# RCMx1_Rev_05.net
KiCad netlist of a schematic drawn in EAGLE
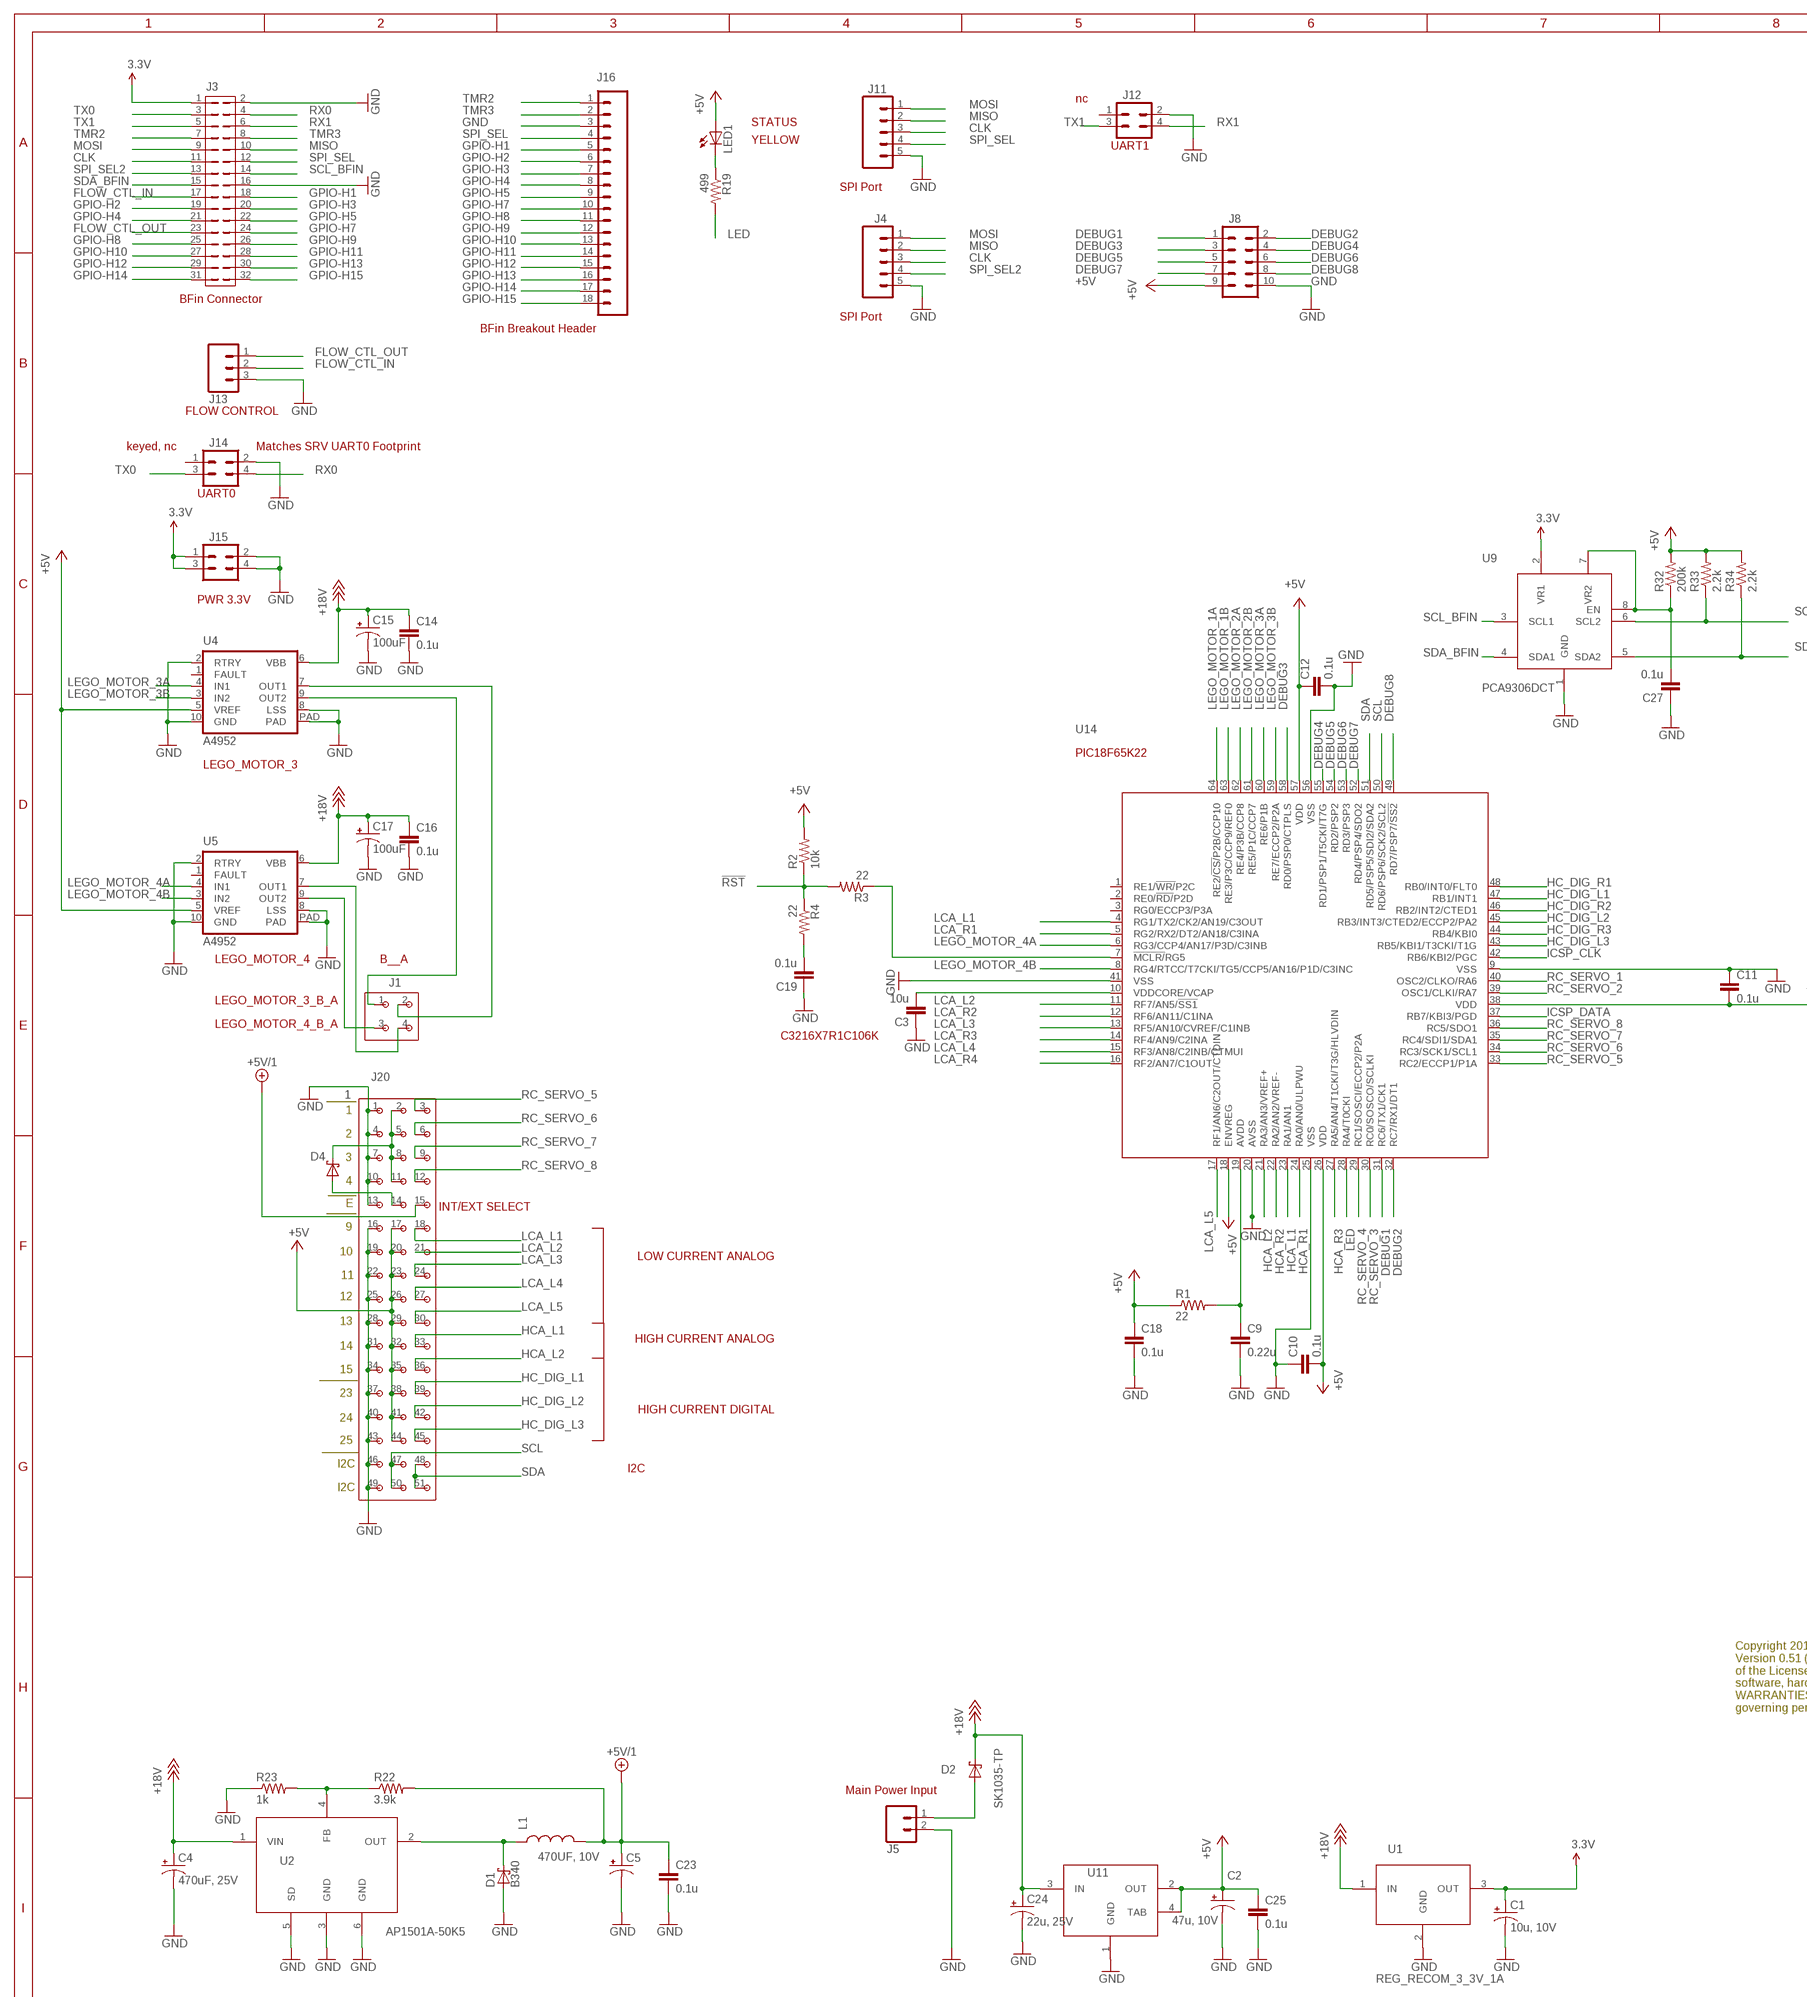
[diagram p0: schematic, sheet 1, part 1 of 2]
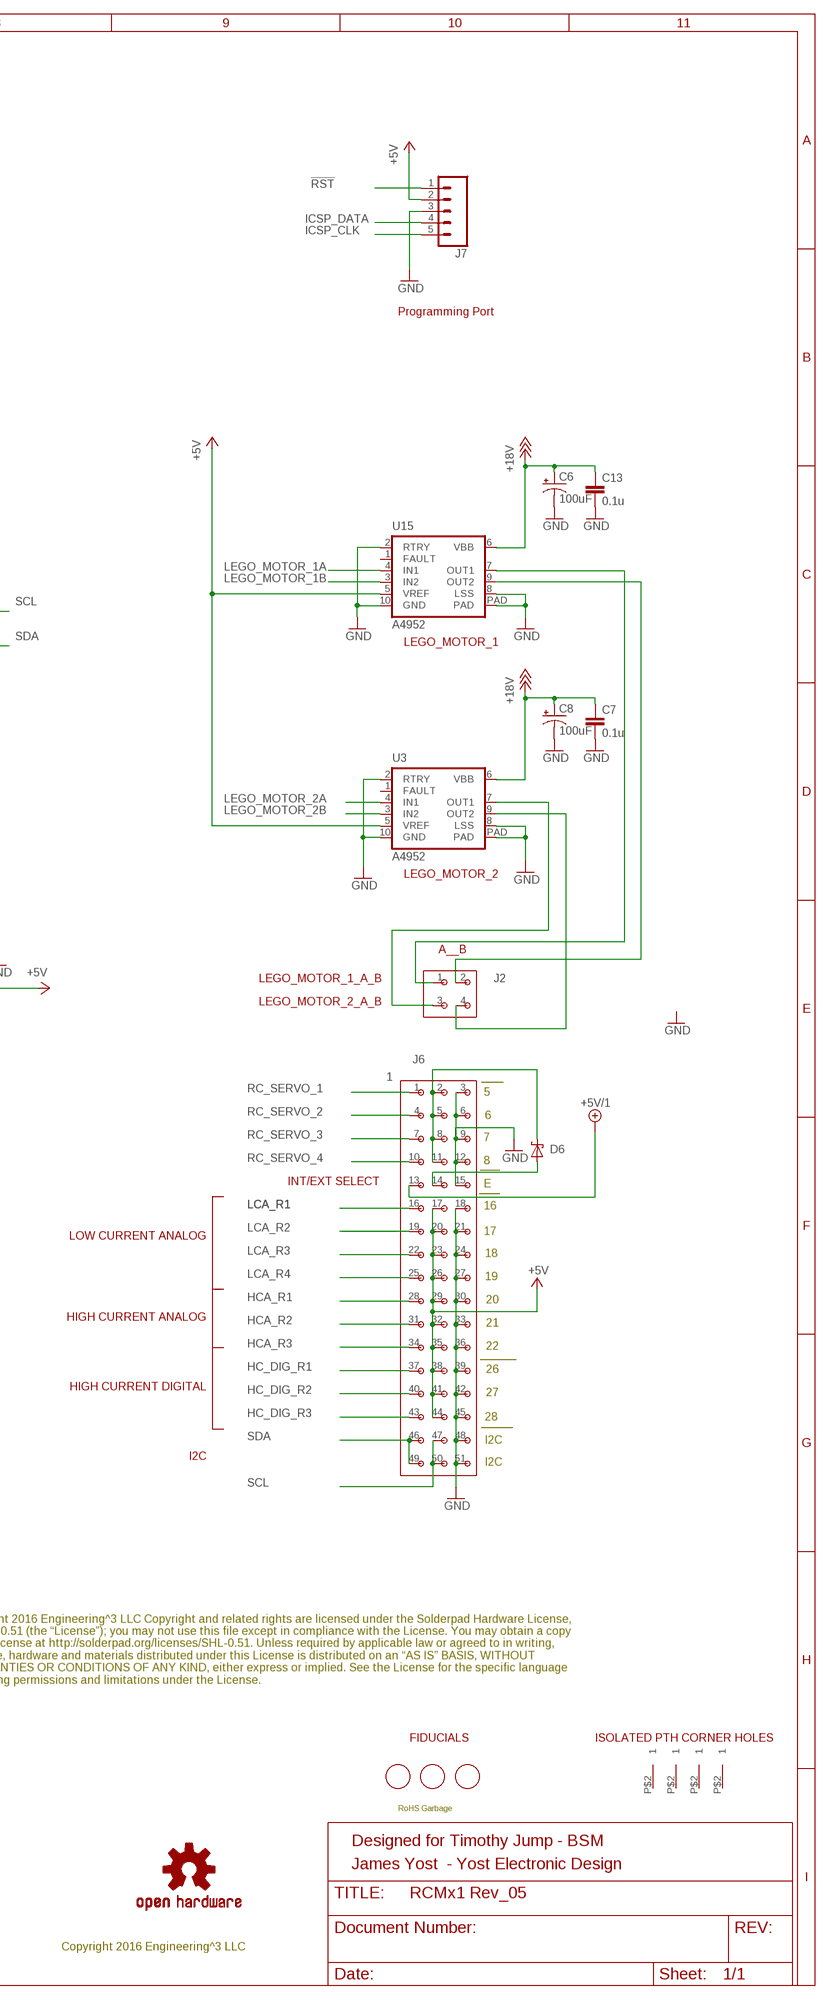
[diagram p1: schematic, sheet 1, part 2 of 2]

(export (version "E")
  (design (tool "Eeschema 10.0.6"))
  (components
    (comp (ref "C1")
      (value "10u, 10V")
      (footprint "eagle-import:EIA3216")
      (libsource (lib "eagle-import") (part "CAP_POL1206"))
    )
    (comp (ref "C2")
      (value "47u, 10V")
      (footprint "eagle-import:CAP1210_POL")
      (libsource (lib "eagle-import") (part "CAP_1210_POL"))
    )
    (comp (ref "C3")
      (value "10u")
      (footprint "eagle-import:1206")
      (libsource (lib "eagle-import") (part "CAP1206"))
    )
    (comp (ref "C4")
      (value "470uF, 25V")
      (footprint "eagle-import:PANASONIC_G")
      (libsource (lib "eagle-import") (part "CAP_POLG"))
    )
    (comp (ref "C5")
      (value "470UF, 10V")
      (footprint "eagle-import:PANASONIC_F")
      (libsource (lib "eagle-import") (part "CAP_ELT_PANASONIC_470UF"))
    )
    (comp (ref "C6")
      (value "100uF")
      (footprint "eagle-import:PANASONIC_D")
      (libsource (lib "eagle-import") (part "CAP_POLD"))
    )
    (comp (ref "C7")
      (value "0.1u")
      (footprint "eagle-import:0805")
      (libsource (lib "eagle-import") (part "CAP0805"))
    )
    (comp (ref "C8")
      (value "100uF")
      (footprint "eagle-import:PANASONIC_D")
      (libsource (lib "eagle-import") (part "CAP_POLD"))
    )
    (comp (ref "C9")
      (value "0.22u")
      (footprint "eagle-import:0805")
      (libsource (lib "eagle-import") (part "CAP0805"))
    )
    (comp (ref "C10")
      (value "0.1u")
      (footprint "eagle-import:0805")
      (libsource (lib "eagle-import") (part "CAP0805"))
    )
    (comp (ref "C11")
      (value "0.1u")
      (footprint "eagle-import:0805")
      (libsource (lib "eagle-import") (part "CAP0805"))
    )
    (comp (ref "C12")
      (value "0.1u")
      (footprint "eagle-import:0805")
      (libsource (lib "eagle-import") (part "CAP0805"))
    )
    (comp (ref "C13")
      (value "0.1u")
      (footprint "eagle-import:0805")
      (libsource (lib "eagle-import") (part "CAP0805"))
    )
    (comp (ref "C14")
      (value "0.1u")
      (footprint "eagle-import:0805")
      (libsource (lib "eagle-import") (part "CAP0805"))
    )
    (comp (ref "C15")
      (value "100uF")
      (footprint "eagle-import:PANASONIC_D")
      (libsource (lib "eagle-import") (part "CAP_POLD"))
    )
    (comp (ref "C16")
      (value "0.1u")
      (footprint "eagle-import:0805")
      (libsource (lib "eagle-import") (part "CAP0805"))
    )
    (comp (ref "C17")
      (value "100uF")
      (footprint "eagle-import:PANASONIC_D")
      (libsource (lib "eagle-import") (part "CAP_POLD"))
    )
    (comp (ref "C18")
      (value "0.1u")
      (footprint "eagle-import:0805")
      (libsource (lib "eagle-import") (part "CAP0805"))
    )
    (comp (ref "C19")
      (value "0.1u")
      (footprint "eagle-import:0805")
      (libsource (lib "eagle-import") (part "CAP0805"))
    )
    (comp (ref "C23")
      (value "0.1u")
      (footprint "eagle-import:0805")
      (libsource (lib "eagle-import") (part "CAP0805"))
    )
    (comp (ref "C24")
      (value "22u, 25V")
      (footprint "eagle-import:CAP1210_POL")
      (libsource (lib "eagle-import") (part "CAP_1210_POL"))
    )
    (comp (ref "C25")
      (value "0.1u")
      (footprint "eagle-import:0805")
      (libsource (lib "eagle-import") (part "CAP0805"))
    )
    (comp (ref "C27")
      (value "0.1u")
      (footprint "eagle-import:0805")
      (libsource (lib "eagle-import") (part "CAP0805"))
    )
    (comp (ref "D1")
      (value "B340")
      (footprint "eagle-import:SMA_DO214AC")
      (libsource (lib "eagle-import") (part "B340"))
    )
    (comp (ref "D2")
      (value "SK1035-TP")
      (footprint "eagle-import:DO214AB")
      (libsource (lib "eagle-import") (part "SK1035-TP"))
    )
    (comp (ref "D4")
      (value "SK1035-TP")
      (footprint "eagle-import:DO214AB")
      (libsource (lib "eagle-import") (part "SK1035-TP"))
    )
    (comp (ref "D6")
      (value "SK1035-TP")
      (footprint "eagle-import:DO214AB")
      (libsource (lib "eagle-import") (part "SK1035-TP"))
    )
    (comp (ref "FID1")
      (value "FIDUCIAL")
      (footprint "eagle-import:FIDUCIAL_1MM")
      (libsource (lib "eagle-import") (part "FIDUCIAL"))
    )
    (comp (ref "FID2")
      (value "FIDUCIAL")
      (footprint "eagle-import:FIDUCIAL_1MM")
      (libsource (lib "eagle-import") (part "FIDUCIAL"))
    )
    (comp (ref "FID3")
      (value "FIDUCIAL")
      (footprint "eagle-import:FIDUCIAL_1MM")
      (libsource (lib "eagle-import") (part "FIDUCIAL"))
    )
    (comp (ref "J1")
      (value "CON_2X2_0_100")
      (footprint "eagle-import:CON_2X2_0_100")
      (libsource (lib "eagle-import") (part "CON_2X2_0_100"))
    )
    (comp (ref "J2")
      (value "CON_2X2_0_100")
      (footprint "eagle-import:CON_2X2_0_100")
      (libsource (lib "eagle-import") (part "CON_2X2_0_100"))
    )
    (comp (ref "J3")
      (value "CON_2X16_0_100")
      (footprint "eagle-import:CON_2X16_0_100")
      (libsource (lib "eagle-import") (part "CON_2X16_0_100"))
    )
    (comp (ref "J4")
      (value "M05PTH")
      (footprint "eagle-import:1X05")
      (libsource (lib "eagle-import") (part "M05PTH"))
    )
    (comp (ref "J5")
      (value "M02NG")
      (footprint "eagle-import:1X02")
      (libsource (lib "eagle-import") (part "M02NG"))
    )
    (comp (ref "J6")
      (value "CON_3X17_0_100")
      (footprint "eagle-import:CON_3X17_0_100")
      (libsource (lib "eagle-import") (part "CON_3X17_0_100"))
    )
    (comp (ref "J7")
      (value "M05PTH")
      (footprint "eagle-import:1X05")
      (libsource (lib "eagle-import") (part "SparkFun-Connectors_M05PTH"))
    )
    (comp (ref "J8")
      (value "M05X2PTH")
      (footprint "eagle-import:AVR_ICSP")
      (libsource (lib "eagle-import") (part "M05X2PTH"))
    )
    (comp (ref "J11")
      (value "M05PTH")
      (footprint "eagle-import:1X05")
      (libsource (lib "eagle-import") (part "M05PTH"))
    )
    (comp (ref "J12")
      (value "CON2X2")
      (footprint "eagle-import:CON2X2")
      (libsource (lib "eagle-import") (part "CON2X2"))
    )
    (comp (ref "J13")
      (value "M03PTH")
      (footprint "eagle-import:1X03")
      (libsource (lib "eagle-import") (part "M03PTH"))
    )
    (comp (ref "J14")
      (value "CON2X2")
      (footprint "eagle-import:CON2X2")
      (libsource (lib "eagle-import") (part "CON2X2"))
    )
    (comp (ref "J15")
      (value "CON2X2")
      (footprint "eagle-import:CON2X2")
      (libsource (lib "eagle-import") (part "CON2X2"))
    )
    (comp (ref "J16")
      (value "CON1X18")
      (footprint "eagle-import:CON1X18")
      (libsource (lib "eagle-import") (part "CON1X18"))
    )
    (comp (ref "J20")
      (value "CON_3X17_0_100")
      (footprint "eagle-import:CON_3X17_0_100")
      (libsource (lib "eagle-import") (part "CON_3X17_0_100"))
    )
    (comp (ref "L1")
      (value "IND_47UH_COILTRONICS_2_95A")
      (footprint "eagle-import:IND_PADS_SMT")
      (libsource (lib "eagle-import") (part "IND_47UH_COILTRONICS_2_95A"))
    )
    (comp (ref "LED1")
      (value "LEDCHIP-LED0805")
      (footprint "eagle-import:CHIP-LED0805")
      (libsource (lib "eagle-import") (part "LEDCHIP-LED0805"))
    )
    (comp (ref "LOGO3")
      (value "OSHW-LOGOM")
      (footprint "eagle-import:OSHW-LOGO-M")
      (libsource (lib "eagle-import") (part "OSHW-LOGOM"))
    )
    (comp (ref "R1")
      (value "22")
      (footprint "eagle-import:0805")
      (libsource (lib "eagle-import") (part "RESISTOR"))
    )
    (comp (ref "R2")
      (value "10k")
      (footprint "eagle-import:0805")
      (libsource (lib "eagle-import") (part "RESISTOR"))
    )
    (comp (ref "R3")
      (value "22")
      (footprint "eagle-import:0805")
      (libsource (lib "eagle-import") (part "RESISTOR"))
    )
    (comp (ref "R4")
      (value "22")
      (footprint "eagle-import:0805")
      (libsource (lib "eagle-import") (part "RESISTOR"))
    )
    (comp (ref "R19")
      (value "499")
      (footprint "eagle-import:0805")
      (libsource (lib "eagle-import") (part "RESISTOR"))
    )
    (comp (ref "R22")
      (value "3.9k")
      (footprint "eagle-import:0805")
      (libsource (lib "eagle-import") (part "RESISTOR"))
    )
    (comp (ref "R23")
      (value "1k")
      (footprint "eagle-import:0805")
      (libsource (lib "eagle-import") (part "RESISTOR"))
    )
    (comp (ref "R32")
      (value "200k")
      (footprint "eagle-import:0805")
      (libsource (lib "eagle-import") (part "RESISTOR"))
    )
    (comp (ref "R33")
      (value "2.2k")
      (footprint "eagle-import:0805")
      (libsource (lib "eagle-import") (part "RESISTOR"))
    )
    (comp (ref "R34")
      (value "2.2k")
      (footprint "eagle-import:0805")
      (libsource (lib "eagle-import") (part "RESISTOR"))
    )
    (comp (ref "U$1")
      (value "GNDPAD")
      (footprint "eagle-import:GNDPAD")
      (libsource (lib "eagle-import") (part "GNDPAD"))
    )
    (comp (ref "U$2")
      (value "GNDPAD")
      (footprint "eagle-import:GNDPAD")
      (libsource (lib "eagle-import") (part "GNDPAD"))
    )
    (comp (ref "U$3")
      (value "ROHS_GARBAGE")
      (footprint "eagle-import:ROHS_GARBAGE_5MM")
      (libsource (lib "eagle-import") (part "ROHS_GARBAGE"))
    )
    (comp (ref "U$7")
      (value "GNDPAD")
      (footprint "eagle-import:GNDPAD")
      (libsource (lib "eagle-import") (part "GNDPAD"))
    )
    (comp (ref "U$8")
      (value "GNDPAD")
      (footprint "eagle-import:GNDPAD")
      (libsource (lib "eagle-import") (part "GNDPAD"))
    )
    (comp (ref "U1")
      (value "REG_RECOM_3_3V_1A")
      (footprint "eagle-import:REG_RECOM_3_3V_1A")
      (libsource (lib "eagle-import") (part "REG_RECOM_3_3V_1A"))
    )
    (comp (ref "U2")
      (value "AP1501A-50K5")
      (footprint "eagle-import:TO263-5")
      (libsource (lib "eagle-import") (part "AP1501A-50K5"))
    )
    (comp (ref "U3")
      (value "A4952")
      (footprint "eagle-import:MSOP10_W_THERMAL_PAD")
      (libsource (lib "eagle-import") (part "A4952"))
    )
    (comp (ref "U4")
      (value "A4952")
      (footprint "eagle-import:MSOP10_W_THERMAL_PAD")
      (libsource (lib "eagle-import") (part "A4952"))
    )
    (comp (ref "U5")
      (value "A4952")
      (footprint "eagle-import:MSOP10_W_THERMAL_PAD")
      (libsource (lib "eagle-import") (part "A4952"))
    )
    (comp (ref "U9")
      (value "PCA9306DCT")
      (footprint "eagle-import:TEST08")
      (libsource (lib "eagle-import") (part "PCA9306DCT"))
    )
    (comp (ref "U11")
      (value "TLV1117-5")
      (footprint "eagle-import:SOT223")
      (libsource (lib "eagle-import") (part "TLV1117-5"))
    )
    (comp (ref "U14")
      (value "MICRO_C_PIC18F65K22")
      (footprint "eagle-import:64PIN_TQFP_10X10X1MM")
      (libsource (lib "eagle-import") (part "MICRO_C_PIC18F65K22"))
    )
    (comp (ref "U15")
      (value "A4952")
      (footprint "eagle-import:MSOP10_W_THERMAL_PAD")
      (libsource (lib "eagle-import") (part "A4952"))
    )
  )
  (nets
    (net (code "1") (name "+5V") (class "Default")
      (node (ref "C10") (pin "2") (pinfunction "2_2") (pintype "passive"))
      (node (ref "C11") (pin "2") (pinfunction "2_2") (pintype "passive"))
      (node (ref "C12") (pin "1") (pinfunction "1_1") (pintype "passive"))
      (node (ref "C18") (pin "1") (pinfunction "1_1") (pintype "passive"))
      (node (ref "C2") (pin "1") (pinfunction "+_1") (pintype "passive"))
      (node (ref "C25") (pin "1") (pinfunction "1_1") (pintype "passive"))
      (node (ref "J20") (pin "17") (pinfunction "17_17") (pintype "passive"))
      (node (ref "J20") (pin "20") (pinfunction "20_20") (pintype "passive"))
      (node (ref "J20") (pin "23") (pinfunction "23_23") (pintype "passive"))
      (node (ref "J20") (pin "26") (pinfunction "26_26") (pintype "passive"))
      (node (ref "J20") (pin "29") (pinfunction "29_29") (pintype "passive"))
      (node (ref "J20") (pin "32") (pinfunction "32_32") (pintype "passive"))
      (node (ref "J20") (pin "35") (pinfunction "35_35") (pintype "passive"))
      (node (ref "J20") (pin "38") (pinfunction "38_38") (pintype "passive"))
      (node (ref "J20") (pin "41") (pinfunction "41_41") (pintype "passive"))
      (node (ref "J20") (pin "44") (pinfunction "44_44") (pintype "passive"))
      (node (ref "J6") (pin "17") (pinfunction "17_17") (pintype "passive"))
      (node (ref "J6") (pin "20") (pinfunction "20_20") (pintype "passive"))
      (node (ref "J6") (pin "23") (pinfunction "23_23") (pintype "passive"))
      (node (ref "J6") (pin "26") (pinfunction "26_26") (pintype "passive"))
      (node (ref "J6") (pin "29") (pinfunction "29_29") (pintype "passive"))
      (node (ref "J6") (pin "32") (pinfunction "32_32") (pintype "passive"))
      (node (ref "J6") (pin "35") (pinfunction "35_35") (pintype "passive"))
      (node (ref "J6") (pin "38") (pinfunction "38_38") (pintype "passive"))
      (node (ref "J6") (pin "41") (pinfunction "41_41") (pintype "passive"))
      (node (ref "J6") (pin "44") (pinfunction "44_44") (pintype "passive"))
      (node (ref "J7") (pin "2") (pinfunction "2_2") (pintype "passive"))
      (node (ref "J8") (pin "9") (pinfunction "9_9") (pintype "passive"))
      (node (ref "LED1") (pin "A") (pinfunction "A_A") (pintype "passive"))
      (node (ref "R1") (pin "1") (pinfunction "1_1") (pintype "passive"))
      (node (ref "R2") (pin "2") (pinfunction "2_2") (pintype "passive"))
      (node (ref "R32") (pin "2") (pinfunction "2_2") (pintype "passive"))
      (node (ref "R33") (pin "2") (pinfunction "2_2") (pintype "passive"))
      (node (ref "R34") (pin "2") (pinfunction "2_2") (pintype "passive"))
      (node (ref "U11") (pin "2") (pinfunction "OUT_2") (pintype "bidirectional"))
      (node (ref "U11") (pin "4") (pinfunction "TAB_4") (pintype "bidirectional"))
      (node (ref "U14") (pin "18") (pinfunction "ENVREG_18") (pintype "input"))
      (node (ref "U14") (pin "26") (pinfunction "VDD_26") (pintype "power_in"))
      (node (ref "U14") (pin "38") (pinfunction "VDD_38") (pintype "power_in"))
      (node (ref "U14") (pin "57") (pinfunction "VDD_57") (pintype "power_in"))
      (node (ref "U15") (pin "5") (pinfunction "VREF_5") (pintype "passive"))
      (node (ref "U3") (pin "5") (pinfunction "VREF_5") (pintype "passive"))
      (node (ref "U4") (pin "5") (pinfunction "VREF_5") (pintype "passive"))
      (node (ref "U5") (pin "5") (pinfunction "VREF_5") (pintype "passive"))
    )
    (net (code "2") (name "+5V{slash}1") (class "Default")
      (node (ref "C23") (pin "1") (pinfunction "1_1") (pintype "passive"))
      (node (ref "C5") (pin "+") (pinfunction "+_+") (pintype "passive"))
      (node (ref "J20") (pin "15") (pinfunction "15_15") (pintype "passive"))
      (node (ref "J6") (pin "13") (pinfunction "13_13") (pintype "passive"))
      (node (ref "L1") (pin "2") (pinfunction "2_2") (pintype "passive"))
      (node (ref "R22") (pin "2") (pinfunction "2_2") (pintype "passive"))
    )
    (net (code "3") (name "+18V") (class "Default")
      (node (ref "C13") (pin "1") (pinfunction "1_1") (pintype "passive"))
      (node (ref "C14") (pin "1") (pinfunction "1_1") (pintype "passive"))
      (node (ref "C15") (pin "+") (pinfunction "+_+") (pintype "passive"))
      (node (ref "C16") (pin "1") (pinfunction "1_1") (pintype "passive"))
      (node (ref "C17") (pin "+") (pinfunction "+_+") (pintype "passive"))
      (node (ref "C24") (pin "1") (pinfunction "+_1") (pintype "passive"))
      (node (ref "C4") (pin "+") (pinfunction "+_+") (pintype "passive"))
      (node (ref "C6") (pin "+") (pinfunction "+_+") (pintype "passive"))
      (node (ref "C7") (pin "1") (pinfunction "1_1") (pintype "passive"))
      (node (ref "C8") (pin "+") (pinfunction "+_+") (pintype "passive"))
      (node (ref "D2") (pin "1") (pinfunction "C_1") (pintype "passive"))
      (node (ref "U1") (pin "1") (pinfunction "IN_1") (pintype "bidirectional"))
      (node (ref "U11") (pin "3") (pinfunction "IN_3") (pintype "bidirectional"))
      (node (ref "U15") (pin "6") (pinfunction "VBB_6") (pintype "input"))
      (node (ref "U2") (pin "1") (pinfunction "VIN_1") (pintype "bidirectional"))
      (node (ref "U3") (pin "6") (pinfunction "VBB_6") (pintype "input"))
      (node (ref "U4") (pin "6") (pinfunction "VBB_6") (pintype "input"))
      (node (ref "U5") (pin "6") (pinfunction "VBB_6") (pintype "input"))
    )
    (net (code "4") (name "/CLK") (class "Default")
      (node (ref "J11") (pin "3") (pinfunction "3_3") (pintype "passive"))
      (node (ref "J3") (pin "11") (pinfunction "11_11") (pintype "passive"))
      (node (ref "J4") (pin "3") (pinfunction "3_3") (pintype "passive"))
    )
    (net (code "5") (name "/DEBUG1") (class "Default")
      (node (ref "J8") (pin "1") (pinfunction "1_1") (pintype "passive"))
      (node (ref "U14") (pin "31") (pinfunction "RC6/TX1/CK1_31") (pintype "bidirectional"))
    )
    (net (code "6") (name "/DEBUG2") (class "Default")
      (node (ref "J8") (pin "2") (pinfunction "2_2") (pintype "passive"))
      (node (ref "U14") (pin "32") (pinfunction "RC7/RX1/DT1_32") (pintype "bidirectional"))
    )
    (net (code "7") (name "/DEBUG3") (class "Default")
      (node (ref "J8") (pin "3") (pinfunction "3_3") (pintype "passive"))
      (node (ref "U14") (pin "58") (pinfunction "RD0/PSP0/CTPLS_58") (pintype "bidirectional"))
    )
    (net (code "8") (name "/DEBUG4") (class "Default")
      (node (ref "J8") (pin "4") (pinfunction "4_4") (pintype "passive"))
      (node (ref "U14") (pin "55") (pinfunction "RD1/PSP1/T5CKI/T7G_55") (pintype "bidirectional"))
    )
    (net (code "9") (name "/DEBUG5") (class "Default")
      (node (ref "J8") (pin "5") (pinfunction "5_5") (pintype "passive"))
      (node (ref "U14") (pin "54") (pinfunction "RD2/PSP2_54") (pintype "bidirectional"))
    )
    (net (code "10") (name "/DEBUG6") (class "Default")
      (node (ref "J8") (pin "6") (pinfunction "6_6") (pintype "passive"))
      (node (ref "U14") (pin "53") (pinfunction "RD3/PSP3_53") (pintype "bidirectional"))
    )
    (net (code "11") (name "/DEBUG7") (class "Default")
      (node (ref "J8") (pin "7") (pinfunction "7_7") (pintype "passive"))
      (node (ref "U14") (pin "52") (pinfunction "RD4/PSP4/SDO2_52") (pintype "bidirectional"))
    )
    (net (code "12") (name "/DEBUG8") (class "Default")
      (node (ref "J8") (pin "8") (pinfunction "8_8") (pintype "passive"))
      (node (ref "U14") (pin "49") (pinfunction "RD7/PSP7/~{SS2}_49") (pintype "bidirectional"))
    )
    (net (code "13") (name "/FLOW_CTL_IN") (class "Default")
      (node (ref "J13") (pin "2") (pinfunction "2_2") (pintype "passive"))
      (node (ref "J3") (pin "17") (pinfunction "17_17") (pintype "passive"))
    )
    (net (code "14") (name "/FLOW_CTL_OUT") (class "Default")
      (node (ref "J13") (pin "1") (pinfunction "1_1") (pintype "passive"))
      (node (ref "J3") (pin "23") (pinfunction "23_23") (pintype "passive"))
    )
    (net (code "15") (name "/GPIO-H1") (class "Default")
      (node (ref "J16") (pin "5") (pinfunction "5_5") (pintype "passive"))
      (node (ref "J3") (pin "18") (pinfunction "18_18") (pintype "passive"))
    )
    (net (code "16") (name "/GPIO-H2") (class "Default")
      (node (ref "J16") (pin "6") (pinfunction "6_6") (pintype "passive"))
      (node (ref "J3") (pin "19") (pinfunction "19_19") (pintype "passive"))
    )
    (net (code "17") (name "/GPIO-H3") (class "Default")
      (node (ref "J16") (pin "7") (pinfunction "7_7") (pintype "passive"))
      (node (ref "J3") (pin "20") (pinfunction "20_20") (pintype "passive"))
    )
    (net (code "18") (name "/GPIO-H4") (class "Default")
      (node (ref "J16") (pin "8") (pinfunction "8_8") (pintype "passive"))
      (node (ref "J3") (pin "21") (pinfunction "21_21") (pintype "passive"))
    )
    (net (code "19") (name "/GPIO-H5") (class "Default")
      (node (ref "J16") (pin "9") (pinfunction "9_9") (pintype "passive"))
      (node (ref "J3") (pin "22") (pinfunction "22_22") (pintype "passive"))
    )
    (net (code "20") (name "/GPIO-H7") (class "Default")
      (node (ref "J16") (pin "10") (pinfunction "10_10") (pintype "passive"))
      (node (ref "J3") (pin "24") (pinfunction "24_24") (pintype "passive"))
    )
    (net (code "21") (name "/GPIO-H8") (class "Default")
      (node (ref "J16") (pin "11") (pinfunction "11_11") (pintype "passive"))
      (node (ref "J3") (pin "25") (pinfunction "25_25") (pintype "passive"))
    )
    (net (code "22") (name "/GPIO-H9") (class "Default")
      (node (ref "J16") (pin "12") (pinfunction "12_12") (pintype "passive"))
      (node (ref "J3") (pin "26") (pinfunction "26_26") (pintype "passive"))
    )
    (net (code "23") (name "/GPIO-H10") (class "Default")
      (node (ref "J16") (pin "13") (pinfunction "13_13") (pintype "passive"))
      (node (ref "J3") (pin "27") (pinfunction "27_27") (pintype "passive"))
    )
    (net (code "24") (name "/GPIO-H11") (class "Default")
      (node (ref "J16") (pin "14") (pinfunction "14_14") (pintype "passive"))
      (node (ref "J3") (pin "28") (pinfunction "28_28") (pintype "passive"))
    )
    (net (code "25") (name "/GPIO-H12") (class "Default")
      (node (ref "J16") (pin "15") (pinfunction "15_15") (pintype "passive"))
      (node (ref "J3") (pin "29") (pinfunction "29_29") (pintype "passive"))
    )
    (net (code "26") (name "/GPIO-H13") (class "Default")
      (node (ref "J16") (pin "16") (pinfunction "16_16") (pintype "passive"))
      (node (ref "J3") (pin "30") (pinfunction "30_30") (pintype "passive"))
    )
    (net (code "27") (name "/GPIO-H14") (class "Default")
      (node (ref "J16") (pin "17") (pinfunction "17_17") (pintype "passive"))
      (node (ref "J3") (pin "31") (pinfunction "31_31") (pintype "passive"))
    )
    (net (code "28") (name "/GPIO-H15") (class "Default")
      (node (ref "J16") (pin "18") (pinfunction "18_18") (pintype "passive"))
      (node (ref "J3") (pin "32") (pinfunction "32_32") (pintype "passive"))
    )
    (net (code "29") (name "/HCA_L1") (class "Default")
      (node (ref "J20") (pin "33") (pinfunction "33_33") (pintype "passive"))
      (node (ref "U14") (pin "23") (pinfunction "RA1/AN1_23") (pintype "bidirectional"))
    )
    (net (code "30") (name "/HCA_L2") (class "Default")
      (node (ref "J20") (pin "36") (pinfunction "36_36") (pintype "passive"))
      (node (ref "U14") (pin "21") (pinfunction "RA3/AN3/VREF+_21") (pintype "bidirectional"))
    )
    (net (code "31") (name "/HCA_R1") (class "Default")
      (node (ref "J6") (pin "28") (pinfunction "28_28") (pintype "passive"))
      (node (ref "U14") (pin "24") (pinfunction "RA0/AN0/ULPWU_24") (pintype "bidirectional"))
    )
    (net (code "32") (name "/HCA_R2") (class "Default")
      (node (ref "J6") (pin "31") (pinfunction "31_31") (pintype "passive"))
      (node (ref "U14") (pin "22") (pinfunction "RA2/AN2/VREF-_22") (pintype "bidirectional"))
    )
    (net (code "33") (name "/HCA_R3") (class "Default")
      (node (ref "J6") (pin "34") (pinfunction "34_34") (pintype "passive"))
      (node (ref "U14") (pin "27") (pinfunction "RA5/AN4/T1CKI/T3G/HLVDIN_27") (pintype "bidirectional"))
    )
    (net (code "34") (name "/HC_DIG_L1") (class "Default")
      (node (ref "J20") (pin "39") (pinfunction "39_39") (pintype "passive"))
      (node (ref "U14") (pin "47") (pinfunction "RB1/INT1_47") (pintype "bidirectional"))
    )
    (net (code "35") (name "/HC_DIG_L2") (class "Default")
      (node (ref "J20") (pin "42") (pinfunction "42_42") (pintype "passive"))
      (node (ref "U14") (pin "45") (pinfunction "RB3/INT3/CTED2/ECCP2/PA2_45") (pintype "bidirectional"))
    )
    (net (code "36") (name "/HC_DIG_L3") (class "Default")
      (node (ref "J20") (pin "45") (pinfunction "45_45") (pintype "passive"))
      (node (ref "U14") (pin "43") (pinfunction "RB5/KBI1/T3CKI/T1G_43") (pintype "bidirectional"))
    )
    (net (code "37") (name "/HC_DIG_R1") (class "Default")
      (node (ref "J6") (pin "37") (pinfunction "37_37") (pintype "passive"))
      (node (ref "U14") (pin "48") (pinfunction "RB0/INT0/FLT0_48") (pintype "bidirectional"))
    )
    (net (code "38") (name "/HC_DIG_R2") (class "Default")
      (node (ref "J6") (pin "40") (pinfunction "40_40") (pintype "passive"))
      (node (ref "U14") (pin "46") (pinfunction "RB2/INT2/CTED1_46") (pintype "bidirectional"))
    )
    (net (code "39") (name "/HC_DIG_R3") (class "Default")
      (node (ref "J6") (pin "43") (pinfunction "43_43") (pintype "passive"))
      (node (ref "U14") (pin "44") (pinfunction "RB4/KBI0_44") (pintype "bidirectional"))
    )
    (net (code "40") (name "/ICSP_CLK") (class "Default")
      (node (ref "J7") (pin "5") (pinfunction "5_5") (pintype "passive"))
      (node (ref "U14") (pin "42") (pinfunction "RB6/KBI2/PGC_42") (pintype "bidirectional"))
    )
    (net (code "41") (name "/ICSP_DATA") (class "Default")
      (node (ref "J7") (pin "4") (pinfunction "4_4") (pintype "passive"))
      (node (ref "U14") (pin "37") (pinfunction "RB7/KBI3/PGD_37") (pintype "bidirectional"))
    )
    (net (code "42") (name "/LCA_L1") (class "Default")
      (node (ref "J20") (pin "18") (pinfunction "18_18") (pintype "passive"))
      (node (ref "U14") (pin "4") (pinfunction "RG1/TX2/CK2/AN19/C3OUT_4") (pintype "bidirectional"))
    )
    (net (code "43") (name "/LCA_L2") (class "Default")
      (node (ref "J20") (pin "21") (pinfunction "21_21") (pintype "passive"))
      (node (ref "U14") (pin "11") (pinfunction "RF7/AN5/~{SS1}_11") (pintype "bidirectional"))
    )
    (net (code "44") (name "/LCA_L3") (class "Default")
      (node (ref "J20") (pin "24") (pinfunction "24_24") (pintype "passive"))
      (node (ref "U14") (pin "13") (pinfunction "RF5/AN10/CVREF/C1INB_13") (pintype "bidirectional"))
    )
    (net (code "45") (name "/LCA_L4") (class "Default")
      (node (ref "J20") (pin "27") (pinfunction "27_27") (pintype "passive"))
      (node (ref "U14") (pin "15") (pinfunction "RF3/AN8/C2INB/CTMUI_15") (pintype "bidirectional"))
    )
    (net (code "46") (name "/LCA_L5") (class "Default")
      (node (ref "J20") (pin "30") (pinfunction "30_30") (pintype "passive"))
      (node (ref "U14") (pin "17") (pinfunction "RF1/AN6/C2OUT/CTDIN_17") (pintype "bidirectional"))
    )
    (net (code "47") (name "/LCA_R1") (class "Default")
      (node (ref "J6") (pin "16") (pinfunction "16_16") (pintype "passive"))
      (node (ref "U14") (pin "5") (pinfunction "RG2/RX2/DT2/AN18/C3INA_5") (pintype "bidirectional"))
    )
    (net (code "48") (name "/LCA_R2") (class "Default")
      (node (ref "J6") (pin "19") (pinfunction "19_19") (pintype "passive"))
      (node (ref "U14") (pin "12") (pinfunction "RF6/AN11/C1INA_12") (pintype "bidirectional"))
    )
    (net (code "49") (name "/LCA_R3") (class "Default")
      (node (ref "J6") (pin "22") (pinfunction "22_22") (pintype "passive"))
      (node (ref "U14") (pin "14") (pinfunction "RF4/AN9/C2INA_14") (pintype "bidirectional"))
    )
    (net (code "50") (name "/LCA_R4") (class "Default")
      (node (ref "J6") (pin "25") (pinfunction "25_25") (pintype "passive"))
      (node (ref "U14") (pin "16") (pinfunction "RF2/AN7/C1OUT_16") (pintype "bidirectional"))
    )
    (net (code "51") (name "/LED") (class "Default")
      (node (ref "R19") (pin "2") (pinfunction "2_2") (pintype "passive"))
      (node (ref "U14") (pin "28") (pinfunction "RA4/T0CKI_28") (pintype "bidirectional"))
    )
    (net (code "52") (name "/LEGO_MOTOR_1A") (class "Default")
      (node (ref "U14") (pin "64") (pinfunction "RE2/~{CS/}P2B/CCP10_64") (pintype "bidirectional"))
      (node (ref "U15") (pin "4") (pinfunction "IN1_4") (pintype "input"))
    )
    (net (code "53") (name "/LEGO_MOTOR_1B") (class "Default")
      (node (ref "U14") (pin "63") (pinfunction "RE3/P3C/CCP9/REF0_63") (pintype "bidirectional"))
      (node (ref "U15") (pin "3") (pinfunction "IN2_3") (pintype "input"))
    )
    (net (code "54") (name "/LEGO_MOTOR_2A") (class "Default")
      (node (ref "U14") (pin "62") (pinfunction "RE4/P3B/CCP8_62") (pintype "bidirectional"))
      (node (ref "U3") (pin "4") (pinfunction "IN1_4") (pintype "input"))
    )
    (net (code "55") (name "/LEGO_MOTOR_2B") (class "Default")
      (node (ref "U14") (pin "61") (pinfunction "RE5/P1C/CCP7_61") (pintype "bidirectional"))
      (node (ref "U3") (pin "3") (pinfunction "IN2_3") (pintype "input"))
    )
    (net (code "56") (name "/LEGO_MOTOR_3A") (class "Default")
      (node (ref "U14") (pin "60") (pinfunction "RE6/P1B_60") (pintype "bidirectional"))
      (node (ref "U4") (pin "4") (pinfunction "IN1_4") (pintype "input"))
    )
    (net (code "57") (name "/LEGO_MOTOR_3B") (class "Default")
      (node (ref "U14") (pin "59") (pinfunction "RE7/ECCP2/P2A_59") (pintype "bidirectional"))
      (node (ref "U4") (pin "3") (pinfunction "IN2_3") (pintype "input"))
    )
    (net (code "58") (name "/LEGO_MOTOR_4A") (class "Default")
      (node (ref "U14") (pin "6") (pinfunction "RG3/CCP4/AN17/P3D/C3INB_6") (pintype "bidirectional"))
      (node (ref "U5") (pin "4") (pinfunction "IN1_4") (pintype "input"))
    )
    (net (code "59") (name "/LEGO_MOTOR_4B") (class "Default")
      (node (ref "U14") (pin "8") (pinfunction "RG4/RTCC/T7CKI/TG5/CCP5/AN16/P1D/C3INC_8") (pintype "bidirectional"))
      (node (ref "U5") (pin "3") (pinfunction "IN2_3") (pintype "input"))
    )
    (net (code "60") (name "/MISO") (class "Default")
      (node (ref "J11") (pin "2") (pinfunction "2_2") (pintype "passive"))
      (node (ref "J3") (pin "10") (pinfunction "10_10") (pintype "passive"))
      (node (ref "J4") (pin "2") (pinfunction "2_2") (pintype "passive"))
    )
    (net (code "61") (name "/MOSI") (class "Default")
      (node (ref "J11") (pin "1") (pinfunction "1_1") (pintype "passive"))
      (node (ref "J3") (pin "9") (pinfunction "9_9") (pintype "passive"))
      (node (ref "J4") (pin "1") (pinfunction "1_1") (pintype "passive"))
    )
    (net (code "62") (name "/RC_SERVO_1") (class "Default")
      (node (ref "J6") (pin "1") (pinfunction "1_1") (pintype "passive"))
      (node (ref "U14") (pin "40") (pinfunction "OSC2/CLKO/RA6_40") (pintype "output"))
    )
    (net (code "63") (name "/RC_SERVO_2") (class "Default")
      (node (ref "J6") (pin "4") (pinfunction "4_4") (pintype "passive"))
      (node (ref "U14") (pin "39") (pinfunction "OSC1/CLKI/RA7_39") (pintype "input"))
    )
    (net (code "64") (name "/RC_SERVO_3") (class "Default")
      (node (ref "J6") (pin "7") (pinfunction "7_7") (pintype "passive"))
      (node (ref "U14") (pin "30") (pinfunction "RC0/SOSCO/SCLKI_30") (pintype "bidirectional"))
    )
    (net (code "65") (name "/RC_SERVO_4") (class "Default")
      (node (ref "J6") (pin "10") (pinfunction "10_10") (pintype "passive"))
      (node (ref "U14") (pin "29") (pinfunction "RC1/SOSCI/ECCP2/P2A_29") (pintype "bidirectional"))
    )
    (net (code "66") (name "/RC_SERVO_5") (class "Default")
      (node (ref "J20") (pin "3") (pinfunction "3_3") (pintype "passive"))
      (node (ref "U14") (pin "33") (pinfunction "RC2/ECCP1/P1A_33") (pintype "bidirectional"))
    )
    (net (code "67") (name "/RC_SERVO_6") (class "Default")
      (node (ref "J20") (pin "6") (pinfunction "6_6") (pintype "passive"))
      (node (ref "U14") (pin "34") (pinfunction "RC3/SCK1/SCL1_34") (pintype "bidirectional"))
    )
    (net (code "68") (name "/RC_SERVO_7") (class "Default")
      (node (ref "J20") (pin "9") (pinfunction "9_9") (pintype "passive"))
      (node (ref "U14") (pin "35") (pinfunction "RC4/SDI1/SDA1_35") (pintype "bidirectional"))
    )
    (net (code "69") (name "/RC_SERVO_8") (class "Default")
      (node (ref "J20") (pin "12") (pinfunction "12_12") (pintype "passive"))
      (node (ref "U14") (pin "36") (pinfunction "RC5/SDO1_36") (pintype "bidirectional"))
    )
    (net (code "70") (name "/RX0") (class "Default")
      (node (ref "J14") (pin "4") (pinfunction "4_4") (pintype "passive"))
      (node (ref "J3") (pin "4") (pinfunction "4_4") (pintype "passive"))
    )
    (net (code "71") (name "/RX1") (class "Default")
      (node (ref "J12") (pin "4") (pinfunction "4_4") (pintype "passive"))
      (node (ref "J3") (pin "6") (pinfunction "6_6") (pintype "passive"))
    )
    (net (code "72") (name "/SCL") (class "Default")
      (node (ref "J20") (pin "47") (pinfunction "47_47") (pintype "passive"))
      (node (ref "J20") (pin "50") (pinfunction "50_50") (pintype "passive"))
      (node (ref "J6") (pin "47") (pinfunction "47_47") (pintype "passive"))
      (node (ref "J6") (pin "50") (pinfunction "50_50") (pintype "passive"))
      (node (ref "R33") (pin "1") (pinfunction "1_1") (pintype "passive"))
      (node (ref "U14") (pin "50") (pinfunction "RD6/PSP6/SCK2/SCL2_50") (pintype "bidirectional"))
      (node (ref "U9") (pin "6") (pinfunction "SCL2_6") (pintype "bidirectional"))
    )
    (net (code "73") (name "/SCL_BFIN") (class "Default")
      (node (ref "J3") (pin "14") (pinfunction "14_14") (pintype "passive"))
      (node (ref "U9") (pin "3") (pinfunction "SCL1_3") (pintype "bidirectional"))
    )
    (net (code "74") (name "/SDA") (class "Default")
      (node (ref "J20") (pin "48") (pinfunction "48_48") (pintype "passive"))
      (node (ref "J20") (pin "51") (pinfunction "51_51") (pintype "passive"))
      (node (ref "J6") (pin "46") (pinfunction "46_46") (pintype "passive"))
      (node (ref "J6") (pin "49") (pinfunction "49_49") (pintype "passive"))
      (node (ref "R34") (pin "1") (pinfunction "1_1") (pintype "passive"))
      (node (ref "U14") (pin "51") (pinfunction "RD5/PSP5/SDI2/SDA2_51") (pintype "bidirectional"))
      (node (ref "U9") (pin "5") (pinfunction "SDA2_5") (pintype "bidirectional"))
    )
    (net (code "75") (name "/SDA_BFIN") (class "Default")
      (node (ref "J3") (pin "15") (pinfunction "15_15") (pintype "passive"))
      (node (ref "U9") (pin "4") (pinfunction "SDA1_4") (pintype "bidirectional"))
    )
    (net (code "76") (name "/SPI_SEL") (class "Default")
      (node (ref "J11") (pin "4") (pinfunction "4_4") (pintype "passive"))
      (node (ref "J16") (pin "4") (pinfunction "4_4") (pintype "passive"))
      (node (ref "J3") (pin "12") (pinfunction "12_12") (pintype "passive"))
    )
    (net (code "77") (name "/SPI_SEL2") (class "Default")
      (node (ref "J3") (pin "13") (pinfunction "13_13") (pintype "passive"))
      (node (ref "J4") (pin "4") (pinfunction "4_4") (pintype "passive"))
    )
    (net (code "78") (name "/TMR2") (class "Default")
      (node (ref "J16") (pin "1") (pinfunction "1_1") (pintype "passive"))
      (node (ref "J3") (pin "7") (pinfunction "7_7") (pintype "passive"))
    )
    (net (code "79") (name "/TMR3") (class "Default")
      (node (ref "J16") (pin "2") (pinfunction "2_2") (pintype "passive"))
      (node (ref "J3") (pin "8") (pinfunction "8_8") (pintype "passive"))
    )
    (net (code "80") (name "/TX0") (class "Default")
      (node (ref "J14") (pin "3") (pinfunction "3_3") (pintype "passive"))
      (node (ref "J3") (pin "3") (pinfunction "3_3") (pintype "passive"))
    )
    (net (code "81") (name "/TX1") (class "Default")
      (node (ref "J12") (pin "3") (pinfunction "3_3") (pintype "passive"))
      (node (ref "J3") (pin "5") (pinfunction "5_5") (pintype "passive"))
    )
    (net (code "82") (name "/~{RST}") (class "Default")
      (node (ref "J7") (pin "1") (pinfunction "1_1") (pintype "passive"))
      (node (ref "R2") (pin "1") (pinfunction "1_1") (pintype "passive"))
      (node (ref "R3") (pin "2") (pinfunction "2_2") (pintype "passive"))
      (node (ref "R4") (pin "1") (pinfunction "1_1") (pintype "passive"))
    )
    (net (code "83") (name "3.3V") (class "Default")
      (node (ref "C1") (pin "A") (pinfunction "+_A") (pintype "passive"))
      (node (ref "J15") (pin "1") (pinfunction "1_1") (pintype "passive"))
      (node (ref "J15") (pin "3") (pinfunction "3_3") (pintype "passive"))
      (node (ref "J3") (pin "1") (pinfunction "1_1") (pintype "passive"))
      (node (ref "U1") (pin "3") (pinfunction "OUT_3") (pintype "bidirectional"))
      (node (ref "U9") (pin "2") (pinfunction "VR1_2") (pintype "bidirectional"))
    )
    (net (code "84") (name "GND") (class "Default")
      (node (ref "C1") (pin "C") (pinfunction "-_C") (pintype "passive"))
      (node (ref "C10") (pin "1") (pinfunction "1_1") (pintype "passive"))
      (node (ref "C11") (pin "1") (pinfunction "1_1") (pintype "passive"))
      (node (ref "C12") (pin "2") (pinfunction "2_2") (pintype "passive"))
      (node (ref "C13") (pin "2") (pinfunction "2_2") (pintype "passive"))
      (node (ref "C14") (pin "2") (pinfunction "2_2") (pintype "passive"))
      (node (ref "C15") (pin "-") (pinfunction "-_-") (pintype "passive"))
      (node (ref "C16") (pin "2") (pinfunction "2_2") (pintype "passive"))
      (node (ref "C17") (pin "-") (pinfunction "-_-") (pintype "passive"))
      (node (ref "C18") (pin "2") (pinfunction "2_2") (pintype "passive"))
      (node (ref "C19") (pin "1") (pinfunction "1_1") (pintype "passive"))
      (node (ref "C2") (pin "2") (pinfunction "-_2") (pintype "passive"))
      (node (ref "C23") (pin "2") (pinfunction "2_2") (pintype "passive"))
      (node (ref "C24") (pin "2") (pinfunction "-_2") (pintype "passive"))
      (node (ref "C25") (pin "2") (pinfunction "2_2") (pintype "passive"))
      (node (ref "C27") (pin "1") (pinfunction "1_1") (pintype "passive"))
      (node (ref "C3") (pin "1") (pinfunction "1_1") (pintype "passive"))
      (node (ref "C4") (pin "-") (pinfunction "-_-") (pintype "passive"))
      (node (ref "C5") (pin "-") (pinfunction "-_-") (pintype "passive"))
      (node (ref "C6") (pin "-") (pinfunction "-_-") (pintype "passive"))
      (node (ref "C7") (pin "2") (pinfunction "2_2") (pintype "passive"))
      (node (ref "C8") (pin "-") (pinfunction "-_-") (pintype "passive"))
      (node (ref "C9") (pin "2") (pinfunction "2_2") (pintype "passive"))
      (node (ref "D1") (pin "A") (pinfunction "A_A") (pintype "passive"))
      (node (ref "J11") (pin "5") (pinfunction "5_5") (pintype "passive"))
      (node (ref "J12") (pin "2") (pinfunction "2_2") (pintype "passive"))
      (node (ref "J13") (pin "3") (pinfunction "3_3") (pintype "passive"))
      (node (ref "J14") (pin "2") (pinfunction "2_2") (pintype "passive"))
      (node (ref "J15") (pin "2") (pinfunction "2_2") (pintype "passive"))
      (node (ref "J15") (pin "4") (pinfunction "4_4") (pintype "passive"))
      (node (ref "J16") (pin "3") (pinfunction "3_3") (pintype "passive"))
      (node (ref "J20") (pin "1") (pinfunction "1_1") (pintype "passive"))
      (node (ref "J20") (pin "10") (pinfunction "10_10") (pintype "passive"))
      (node (ref "J20") (pin "13") (pinfunction "13_13") (pintype "passive"))
      (node (ref "J20") (pin "16") (pinfunction "16_16") (pintype "passive"))
      (node (ref "J20") (pin "19") (pinfunction "19_19") (pintype "passive"))
      (node (ref "J20") (pin "22") (pinfunction "22_22") (pintype "passive"))
      (node (ref "J20") (pin "25") (pinfunction "25_25") (pintype "passive"))
      (node (ref "J20") (pin "28") (pinfunction "28_28") (pintype "passive"))
      (node (ref "J20") (pin "31") (pinfunction "31_31") (pintype "passive"))
      (node (ref "J20") (pin "34") (pinfunction "34_34") (pintype "passive"))
      (node (ref "J20") (pin "37") (pinfunction "37_37") (pintype "passive"))
      (node (ref "J20") (pin "4") (pinfunction "4_4") (pintype "passive"))
      (node (ref "J20") (pin "40") (pinfunction "40_40") (pintype "passive"))
      (node (ref "J20") (pin "43") (pinfunction "43_43") (pintype "passive"))
      (node (ref "J20") (pin "46") (pinfunction "46_46") (pintype "passive"))
      (node (ref "J20") (pin "49") (pinfunction "49_49") (pintype "passive"))
      (node (ref "J20") (pin "7") (pinfunction "7_7") (pintype "passive"))
      (node (ref "J3") (pin "16") (pinfunction "16_16") (pintype "passive"))
      (node (ref "J3") (pin "2") (pinfunction "2_2") (pintype "passive"))
      (node (ref "J4") (pin "5") (pinfunction "5_5") (pintype "passive"))
      (node (ref "J5") (pin "2") (pinfunction "2_2") (pintype "passive"))
      (node (ref "J6") (pin "12") (pinfunction "12_12") (pintype "passive"))
      (node (ref "J6") (pin "15") (pinfunction "15_15") (pintype "passive"))
      (node (ref "J6") (pin "18") (pinfunction "18_18") (pintype "passive"))
      (node (ref "J6") (pin "21") (pinfunction "21_21") (pintype "passive"))
      (node (ref "J6") (pin "24") (pinfunction "24_24") (pintype "passive"))
      (node (ref "J6") (pin "27") (pinfunction "27_27") (pintype "passive"))
      (node (ref "J6") (pin "3") (pinfunction "3_3") (pintype "passive"))
      (node (ref "J6") (pin "30") (pinfunction "30_30") (pintype "passive"))
      (node (ref "J6") (pin "33") (pinfunction "33_33") (pintype "passive"))
      (node (ref "J6") (pin "36") (pinfunction "36_36") (pintype "passive"))
      (node (ref "J6") (pin "39") (pinfunction "39_39") (pintype "passive"))
      (node (ref "J6") (pin "42") (pinfunction "42_42") (pintype "passive"))
      (node (ref "J6") (pin "45") (pinfunction "45_45") (pintype "passive"))
      (node (ref "J6") (pin "48") (pinfunction "48_48") (pintype "passive"))
      (node (ref "J6") (pin "51") (pinfunction "51_51") (pintype "passive"))
      (node (ref "J6") (pin "6") (pinfunction "6_6") (pintype "passive"))
      (node (ref "J6") (pin "9") (pinfunction "9_9") (pintype "passive"))
      (node (ref "J7") (pin "3") (pinfunction "3_3") (pintype "passive"))
      (node (ref "J8") (pin "10") (pinfunction "10_10") (pintype "passive"))
      (node (ref "R23") (pin "1") (pinfunction "1_1") (pintype "passive"))
      (node (ref "U1") (pin "2") (pinfunction "GND_2") (pintype "bidirectional"))
      (node (ref "U11") (pin "1") (pinfunction "GND_1") (pintype "bidirectional"))
      (node (ref "U14") (pin "20") (pinfunction "AVSS_20") (pintype "power_in"))
      (node (ref "U14") (pin "25") (pinfunction "VSS_25") (pintype "power_in"))
      (node (ref "U14") (pin "41") (pinfunction "VSS_41") (pintype "power_in"))
      (node (ref "U14") (pin "56") (pinfunction "VSS_56") (pintype "power_in"))
      (node (ref "U14") (pin "9") (pinfunction "VSS_9") (pintype "power_in"))
      (node (ref "U15") (pin "10") (pinfunction "GND_10") (pintype "power_in"))
      (node (ref "U15") (pin "2") (pinfunction "RTRY_2") (pintype "input"))
      (node (ref "U15") (pin "8") (pinfunction "LSS_8") (pintype "output"))
      (node (ref "U15") (pin "PAD") (pinfunction "PAD_PAD") (pintype "output"))
      (node (ref "U2") (pin "3") (pinfunction "GND_3") (pintype "bidirectional"))
      (node (ref "U2") (pin "5") (pinfunction "SD_5") (pintype "bidirectional"))
      (node (ref "U2") (pin "6") (pinfunction "GND_6") (pintype "bidirectional"))
      (node (ref "U3") (pin "10") (pinfunction "GND_10") (pintype "power_in"))
      (node (ref "U3") (pin "2") (pinfunction "RTRY_2") (pintype "input"))
      (node (ref "U3") (pin "8") (pinfunction "LSS_8") (pintype "output"))
      (node (ref "U3") (pin "PAD") (pinfunction "PAD_PAD") (pintype "output"))
      (node (ref "U4") (pin "10") (pinfunction "GND_10") (pintype "power_in"))
      (node (ref "U4") (pin "2") (pinfunction "RTRY_2") (pintype "input"))
      (node (ref "U4") (pin "8") (pinfunction "LSS_8") (pintype "output"))
      (node (ref "U4") (pin "PAD") (pinfunction "PAD_PAD") (pintype "output"))
      (node (ref "U5") (pin "10") (pinfunction "GND_10") (pintype "power_in"))
      (node (ref "U5") (pin "2") (pinfunction "RTRY_2") (pintype "input"))
      (node (ref "U5") (pin "8") (pinfunction "LSS_8") (pintype "output"))
      (node (ref "U5") (pin "PAD") (pinfunction "PAD_PAD") (pintype "output"))
      (node (ref "U9") (pin "1") (pinfunction "GND_1") (pintype "bidirectional"))
    )
    (net (code "85") (name "Net-(C19-Pad2)") (class "Default")
      (node (ref "C19") (pin "2") (pinfunction "2_2") (pintype "passive"))
      (node (ref "R4") (pin "2") (pinfunction "2_2") (pintype "passive"))
    )
    (net (code "86") (name "Net-(D2-A)") (class "Default")
      (node (ref "D2") (pin "2") (pinfunction "A_2") (pintype "passive"))
      (node (ref "J5") (pin "1") (pinfunction "1_1") (pintype "passive"))
    )
    (net (code "87") (name "Net-(D4-A)") (class "Default")
      (node (ref "D4") (pin "2") (pinfunction "A_2") (pintype "passive"))
      (node (ref "J20") (pin "14") (pinfunction "14_14") (pintype "passive"))
    )
    (net (code "88") (name "Net-(D4-C)") (class "Default")
      (node (ref "D4") (pin "1") (pinfunction "C_1") (pintype "passive"))
      (node (ref "J20") (pin "11") (pinfunction "11_11") (pintype "passive"))
      (node (ref "J20") (pin "2") (pinfunction "2_2") (pintype "passive"))
      (node (ref "J20") (pin "5") (pinfunction "5_5") (pintype "passive"))
      (node (ref "J20") (pin "8") (pinfunction "8_8") (pintype "passive"))
    )
    (net (code "89") (name "Net-(D6-A)") (class "Default")
      (node (ref "D6") (pin "2") (pinfunction "A_2") (pintype "passive"))
      (node (ref "J6") (pin "14") (pinfunction "14_14") (pintype "passive"))
    )
    (net (code "90") (name "Net-(D6-C)") (class "Default")
      (node (ref "D6") (pin "1") (pinfunction "C_1") (pintype "passive"))
      (node (ref "J6") (pin "11") (pinfunction "11_11") (pintype "passive"))
      (node (ref "J6") (pin "2") (pinfunction "2_2") (pintype "passive"))
      (node (ref "J6") (pin "5") (pinfunction "5_5") (pintype "passive"))
      (node (ref "J6") (pin "8") (pinfunction "8_8") (pintype "passive"))
    )
    (net (code "91") (name "Net-(LED1-PadC)") (class "Default")
      (node (ref "LED1") (pin "C") (pinfunction "C_C") (pintype "passive"))
      (node (ref "R19") (pin "1") (pinfunction "1_1") (pintype "passive"))
    )
    (net (code "92") (name "Net-(U2-FB)") (class "Default")
      (node (ref "R22") (pin "1") (pinfunction "1_1") (pintype "passive"))
      (node (ref "R23") (pin "2") (pinfunction "2_2") (pintype "passive"))
      (node (ref "U2") (pin "4") (pinfunction "FB_4") (pintype "bidirectional"))
    )
    (net (code "93") (name "Net-(U2-OUT)") (class "Default")
      (node (ref "D1") (pin "C") (pinfunction "C_C") (pintype "passive"))
      (node (ref "L1") (pin "1") (pinfunction "1_1") (pintype "passive"))
      (node (ref "U2") (pin "2") (pinfunction "OUT_2") (pintype "bidirectional"))
    )
    (net (code "94") (name "Net-(U3-OUT1)") (class "Default")
      (node (ref "J2") (pin "3") (pinfunction "3_3") (pintype "passive"))
      (node (ref "U3") (pin "7") (pinfunction "OUT1_7") (pintype "output"))
    )
    (net (code "95") (name "Net-(U3-OUT2)") (class "Default")
      (node (ref "J2") (pin "4") (pinfunction "4_4") (pintype "passive"))
      (node (ref "U3") (pin "9") (pinfunction "OUT2_9") (pintype "input"))
    )
    (net (code "96") (name "Net-(U4-OUT1)") (class "Default")
      (node (ref "J1") (pin "2") (pinfunction "2_2") (pintype "passive"))
      (node (ref "U4") (pin "7") (pinfunction "OUT1_7") (pintype "output"))
    )
    (net (code "97") (name "Net-(U4-OUT2)") (class "Default")
      (node (ref "J1") (pin "1") (pinfunction "1_1") (pintype "passive"))
      (node (ref "U4") (pin "9") (pinfunction "OUT2_9") (pintype "input"))
    )
    (net (code "98") (name "Net-(U5-OUT1)") (class "Default")
      (node (ref "J1") (pin "4") (pinfunction "4_4") (pintype "passive"))
      (node (ref "U5") (pin "7") (pinfunction "OUT1_7") (pintype "output"))
    )
    (net (code "99") (name "Net-(U5-OUT2)") (class "Default")
      (node (ref "J1") (pin "3") (pinfunction "3_3") (pintype "passive"))
      (node (ref "U5") (pin "9") (pinfunction "OUT2_9") (pintype "input"))
    )
    (net (code "100") (name "Net-(U9-EN)") (class "Default")
      (node (ref "C27") (pin "2") (pinfunction "2_2") (pintype "passive"))
      (node (ref "R32") (pin "1") (pinfunction "1_1") (pintype "passive"))
      (node (ref "U9") (pin "7") (pinfunction "VR2_7") (pintype "bidirectional"))
      (node (ref "U9") (pin "8") (pinfunction "EN_8") (pintype "input"))
    )
    (net (code "101") (name "Net-(U14-AVDD)") (class "Default")
      (node (ref "C9") (pin "1") (pinfunction "1_1") (pintype "passive"))
      (node (ref "R1") (pin "2") (pinfunction "2_2") (pintype "passive"))
      (node (ref "U14") (pin "19") (pinfunction "AVDD_19") (pintype "power_in"))
    )
    (net (code "102") (name "Net-(U14-VDDCORE{slash}VCAP)") (class "Default")
      (node (ref "C3") (pin "2") (pinfunction "2_2") (pintype "passive"))
      (node (ref "U14") (pin "10") (pinfunction "VDDCORE/VCAP_10") (pintype "power_in"))
    )
    (net (code "103") (name "Net-(U14-~{MCLR{slash}}RG5)") (class "Default")
      (node (ref "R3") (pin "1") (pinfunction "1_1") (pintype "passive"))
      (node (ref "U14") (pin "7") (pinfunction "~{MCLR/}RG5_7") (pintype "input"))
    )
    (net (code "104") (name "Net-(U15-OUT1)") (class "Default")
      (node (ref "J2") (pin "1") (pinfunction "1_1") (pintype "passive"))
      (node (ref "U15") (pin "7") (pinfunction "OUT1_7") (pintype "output"))
    )
    (net (code "105") (name "Net-(U15-OUT2)") (class "Default")
      (node (ref "J2") (pin "2") (pinfunction "2_2") (pintype "passive"))
      (node (ref "U15") (pin "9") (pinfunction "OUT2_9") (pintype "input"))
    )
    (net (code "106") (name "unconnected-(J12-Pad1)") (class "Default")
      (node (ref "J12") (pin "1") (pinfunction "1_1") (pintype "passive"))
    )
    (net (code "107") (name "unconnected-(J14-Pad1)") (class "Default")
      (node (ref "J14") (pin "1") (pinfunction "1_1") (pintype "passive"))
    )
    (net (code "108") (name "unconnected-(U$1-1-PadP$2)") (class "Default")
      (node (ref "U$1") (pin "P$2") (pinfunction "1_P$2") (pintype "bidirectional"))
    )
    (net (code "109") (name "unconnected-(U$2-1-PadP$2)") (class "Default")
      (node (ref "U$2") (pin "P$2") (pinfunction "1_P$2") (pintype "bidirectional"))
    )
    (net (code "110") (name "unconnected-(U$7-1-PadP$2)") (class "Default")
      (node (ref "U$7") (pin "P$2") (pinfunction "1_P$2") (pintype "bidirectional"))
    )
    (net (code "111") (name "unconnected-(U$8-1-PadP$2)") (class "Default")
      (node (ref "U$8") (pin "P$2") (pinfunction "1_P$2") (pintype "bidirectional"))
    )
    (net (code "112") (name "unconnected-(U3-FAULT-Pad1)") (class "Default")
      (node (ref "U3") (pin "1") (pinfunction "FAULT_1") (pintype "output"))
    )
    (net (code "113") (name "unconnected-(U4-FAULT-Pad1)") (class "Default")
      (node (ref "U4") (pin "1") (pinfunction "FAULT_1") (pintype "output"))
    )
    (net (code "114") (name "unconnected-(U5-FAULT-Pad1)") (class "Default")
      (node (ref "U5") (pin "1") (pinfunction "FAULT_1") (pintype "output"))
    )
    (net (code "115") (name "unconnected-(U14-RE0{slash}~{RD{slash}}P2D-Pad2)") (class "Default")
      (node (ref "U14") (pin "2") (pinfunction "RE0/~{RD/}P2D_2") (pintype "bidirectional"))
    )
    (net (code "116") (name "unconnected-(U14-RE1{slash}~{WR{slash}}P2C-Pad1)") (class "Default")
      (node (ref "U14") (pin "1") (pinfunction "RE1/~{WR/}P2C_1") (pintype "bidirectional"))
    )
    (net (code "117") (name "unconnected-(U14-RG0{slash}ECCP3{slash}P3A-Pad3)") (class "Default")
      (node (ref "U14") (pin "3") (pinfunction "RG0/ECCP3/P3A_3") (pintype "bidirectional"))
    )
    (net (code "118") (name "unconnected-(U15-FAULT-Pad1)") (class "Default")
      (node (ref "U15") (pin "1") (pinfunction "FAULT_1") (pintype "output"))
    )
  )
)
